# Schematic_v1_0.net
KiCad netlist of a schematic drawn in EAGLE
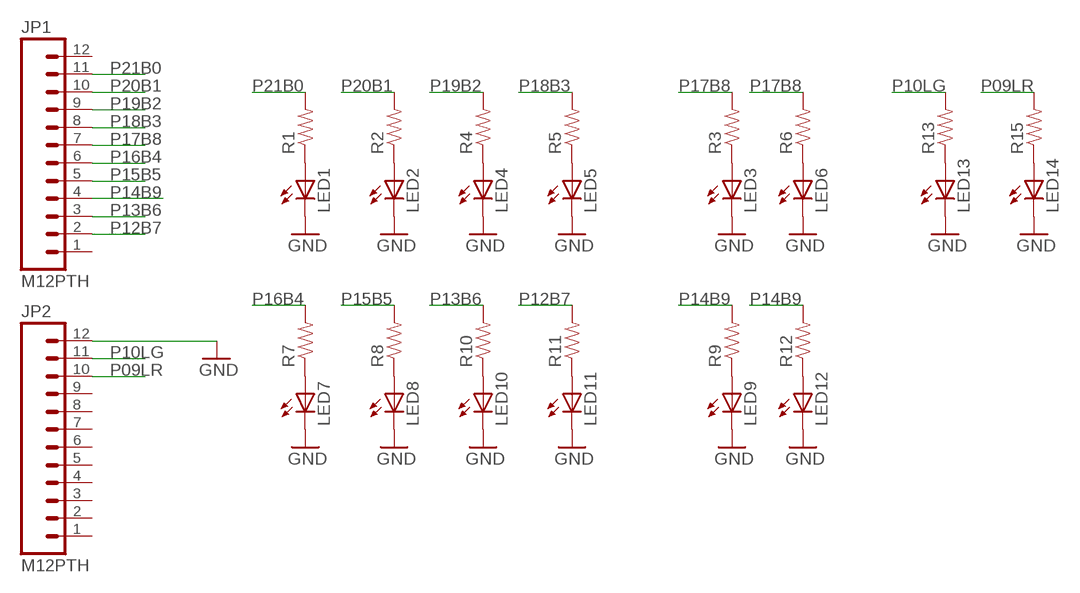
[diagram p0: schematic, sheet 1]

(export (version "E")
  (design (tool "Eeschema 10.0.6"))
  (components
    (comp (ref "JP1")
      (value "M12PTH")
      (footprint "eagle-import:1X12")
      (libsource (lib "eagle-import") (part "M12PTH"))
    )
    (comp (ref "JP2")
      (value "M12PTH")
      (footprint "eagle-import:1X12")
      (libsource (lib "eagle-import") (part "M12PTH"))
    )
    (comp (ref "LED1")
      (value "LEDCHIPLED_0805")
      (footprint "eagle-import:CHIPLED_0805")
      (libsource (lib "eagle-import") (part "LEDCHIPLED_0805"))
    )
    (comp (ref "LED2")
      (value "LEDCHIPLED_0805")
      (footprint "eagle-import:CHIPLED_0805")
      (libsource (lib "eagle-import") (part "LEDCHIPLED_0805"))
    )
    (comp (ref "LED3")
      (value "LEDCHIPLED_0805")
      (footprint "eagle-import:CHIPLED_0805")
      (libsource (lib "eagle-import") (part "LEDCHIPLED_0805"))
    )
    (comp (ref "LED4")
      (value "LEDCHIPLED_0805")
      (footprint "eagle-import:CHIPLED_0805")
      (libsource (lib "eagle-import") (part "LEDCHIPLED_0805"))
    )
    (comp (ref "LED5")
      (value "LEDCHIPLED_0805")
      (footprint "eagle-import:CHIPLED_0805")
      (libsource (lib "eagle-import") (part "LEDCHIPLED_0805"))
    )
    (comp (ref "LED6")
      (value "LEDCHIPLED_0805")
      (footprint "eagle-import:CHIPLED_0805")
      (libsource (lib "eagle-import") (part "LEDCHIPLED_0805"))
    )
    (comp (ref "LED7")
      (value "LEDCHIPLED_0805")
      (footprint "eagle-import:CHIPLED_0805")
      (libsource (lib "eagle-import") (part "LEDCHIPLED_0805"))
    )
    (comp (ref "LED8")
      (value "LEDCHIPLED_0805")
      (footprint "eagle-import:CHIPLED_0805")
      (libsource (lib "eagle-import") (part "LEDCHIPLED_0805"))
    )
    (comp (ref "LED9")
      (value "LEDCHIPLED_0805")
      (footprint "eagle-import:CHIPLED_0805")
      (libsource (lib "eagle-import") (part "LEDCHIPLED_0805"))
    )
    (comp (ref "LED10")
      (value "LEDCHIPLED_0805")
      (footprint "eagle-import:CHIPLED_0805")
      (libsource (lib "eagle-import") (part "LEDCHIPLED_0805"))
    )
    (comp (ref "LED11")
      (value "LEDCHIPLED_0805")
      (footprint "eagle-import:CHIPLED_0805")
      (libsource (lib "eagle-import") (part "LEDCHIPLED_0805"))
    )
    (comp (ref "LED12")
      (value "LEDCHIPLED_0805")
      (footprint "eagle-import:CHIPLED_0805")
      (libsource (lib "eagle-import") (part "LEDCHIPLED_0805"))
    )
    (comp (ref "LED13")
      (value "LEDCHIPLED_0805")
      (footprint "eagle-import:CHIPLED_0805")
      (libsource (lib "eagle-import") (part "LEDCHIPLED_0805"))
    )
    (comp (ref "LED14")
      (value "LEDCHIPLED_0805")
      (footprint "eagle-import:CHIPLED_0805")
      (libsource (lib "eagle-import") (part "LEDCHIPLED_0805"))
    )
    (comp (ref "R1")
      (value "RESISTOR0603-RES")
      (footprint "eagle-import:0603-RES")
      (libsource (lib "eagle-import") (part "RESISTOR0603-RES"))
    )
    (comp (ref "R2")
      (value "RESISTOR0603-RES")
      (footprint "eagle-import:0603-RES")
      (libsource (lib "eagle-import") (part "RESISTOR0603-RES"))
    )
    (comp (ref "R3")
      (value "RESISTOR0603-RES")
      (footprint "eagle-import:0603-RES")
      (libsource (lib "eagle-import") (part "RESISTOR0603-RES"))
    )
    (comp (ref "R4")
      (value "RESISTOR0603-RES")
      (footprint "eagle-import:0603-RES")
      (libsource (lib "eagle-import") (part "RESISTOR0603-RES"))
    )
    (comp (ref "R5")
      (value "RESISTOR0603-RES")
      (footprint "eagle-import:0603-RES")
      (libsource (lib "eagle-import") (part "RESISTOR0603-RES"))
    )
    (comp (ref "R6")
      (value "RESISTOR0603-RES")
      (footprint "eagle-import:0603-RES")
      (libsource (lib "eagle-import") (part "RESISTOR0603-RES"))
    )
    (comp (ref "R7")
      (value "RESISTOR0603-RES")
      (footprint "eagle-import:0603-RES")
      (libsource (lib "eagle-import") (part "RESISTOR0603-RES"))
    )
    (comp (ref "R8")
      (value "RESISTOR0603-RES")
      (footprint "eagle-import:0603-RES")
      (libsource (lib "eagle-import") (part "RESISTOR0603-RES"))
    )
    (comp (ref "R9")
      (value "RESISTOR0603-RES")
      (footprint "eagle-import:0603-RES")
      (libsource (lib "eagle-import") (part "RESISTOR0603-RES"))
    )
    (comp (ref "R10")
      (value "RESISTOR0603-RES")
      (footprint "eagle-import:0603-RES")
      (libsource (lib "eagle-import") (part "RESISTOR0603-RES"))
    )
    (comp (ref "R11")
      (value "RESISTOR0603-RES")
      (footprint "eagle-import:0603-RES")
      (libsource (lib "eagle-import") (part "RESISTOR0603-RES"))
    )
    (comp (ref "R12")
      (value "RESISTOR0603-RES")
      (footprint "eagle-import:0603-RES")
      (libsource (lib "eagle-import") (part "RESISTOR0603-RES"))
    )
    (comp (ref "R13")
      (value "RESISTOR0603-RES")
      (footprint "eagle-import:0603-RES")
      (libsource (lib "eagle-import") (part "RESISTOR0603-RES"))
    )
    (comp (ref "R15")
      (value "RESISTOR0603-RES")
      (footprint "eagle-import:0603-RES")
      (libsource (lib "eagle-import") (part "RESISTOR0603-RES"))
    )
  )
  (nets
    (net (code "1") (name "/P09LR") (class "Default")
      (node (ref "JP2") (pin "10") (pinfunction "10_10") (pintype "passive"))
      (node (ref "R15") (pin "2") (pinfunction "2_2") (pintype "passive"))
    )
    (net (code "2") (name "/P10LG") (class "Default")
      (node (ref "JP2") (pin "11") (pinfunction "11_11") (pintype "passive"))
      (node (ref "R13") (pin "2") (pinfunction "2_2") (pintype "passive"))
    )
    (net (code "3") (name "/P12B7") (class "Default")
      (node (ref "JP1") (pin "2") (pinfunction "2_2") (pintype "passive"))
      (node (ref "R11") (pin "2") (pinfunction "2_2") (pintype "passive"))
    )
    (net (code "4") (name "/P13B6") (class "Default")
      (node (ref "JP1") (pin "3") (pinfunction "3_3") (pintype "passive"))
      (node (ref "R10") (pin "2") (pinfunction "2_2") (pintype "passive"))
    )
    (net (code "5") (name "/P14B9") (class "Default")
      (node (ref "JP1") (pin "4") (pinfunction "4_4") (pintype "passive"))
      (node (ref "R12") (pin "2") (pinfunction "2_2") (pintype "passive"))
      (node (ref "R9") (pin "2") (pinfunction "2_2") (pintype "passive"))
    )
    (net (code "6") (name "/P15B5") (class "Default")
      (node (ref "JP1") (pin "5") (pinfunction "5_5") (pintype "passive"))
      (node (ref "R8") (pin "2") (pinfunction "2_2") (pintype "passive"))
    )
    (net (code "7") (name "/P16B4") (class "Default")
      (node (ref "JP1") (pin "6") (pinfunction "6_6") (pintype "passive"))
      (node (ref "R7") (pin "2") (pinfunction "2_2") (pintype "passive"))
    )
    (net (code "8") (name "/P17B8") (class "Default")
      (node (ref "JP1") (pin "7") (pinfunction "7_7") (pintype "passive"))
      (node (ref "R3") (pin "2") (pinfunction "2_2") (pintype "passive"))
      (node (ref "R6") (pin "2") (pinfunction "2_2") (pintype "passive"))
    )
    (net (code "9") (name "/P18B3") (class "Default")
      (node (ref "JP1") (pin "8") (pinfunction "8_8") (pintype "passive"))
      (node (ref "R5") (pin "2") (pinfunction "2_2") (pintype "passive"))
    )
    (net (code "10") (name "/P19B2") (class "Default")
      (node (ref "JP1") (pin "9") (pinfunction "9_9") (pintype "passive"))
      (node (ref "R4") (pin "2") (pinfunction "2_2") (pintype "passive"))
    )
    (net (code "11") (name "/P20B1") (class "Default")
      (node (ref "JP1") (pin "10") (pinfunction "10_10") (pintype "passive"))
      (node (ref "R2") (pin "2") (pinfunction "2_2") (pintype "passive"))
    )
    (net (code "12") (name "/P21B0") (class "Default")
      (node (ref "JP1") (pin "11") (pinfunction "11_11") (pintype "passive"))
      (node (ref "R1") (pin "2") (pinfunction "2_2") (pintype "passive"))
    )
    (net (code "13") (name "GND") (class "Default")
      (node (ref "JP2") (pin "12") (pinfunction "12_12") (pintype "passive"))
      (node (ref "LED1") (pin "C") (pinfunction "C_C") (pintype "passive"))
      (node (ref "LED10") (pin "C") (pinfunction "C_C") (pintype "passive"))
      (node (ref "LED11") (pin "C") (pinfunction "C_C") (pintype "passive"))
      (node (ref "LED12") (pin "C") (pinfunction "C_C") (pintype "passive"))
      (node (ref "LED13") (pin "C") (pinfunction "C_C") (pintype "passive"))
      (node (ref "LED14") (pin "C") (pinfunction "C_C") (pintype "passive"))
      (node (ref "LED2") (pin "C") (pinfunction "C_C") (pintype "passive"))
      (node (ref "LED3") (pin "C") (pinfunction "C_C") (pintype "passive"))
      (node (ref "LED4") (pin "C") (pinfunction "C_C") (pintype "passive"))
      (node (ref "LED5") (pin "C") (pinfunction "C_C") (pintype "passive"))
      (node (ref "LED6") (pin "C") (pinfunction "C_C") (pintype "passive"))
      (node (ref "LED7") (pin "C") (pinfunction "C_C") (pintype "passive"))
      (node (ref "LED8") (pin "C") (pinfunction "C_C") (pintype "passive"))
      (node (ref "LED9") (pin "C") (pinfunction "C_C") (pintype "passive"))
    )
    (net (code "14") (name "Net-(LED1-PadA)") (class "Default")
      (node (ref "LED1") (pin "A") (pinfunction "A_A") (pintype "passive"))
      (node (ref "R1") (pin "1") (pinfunction "1_1") (pintype "passive"))
    )
    (net (code "15") (name "Net-(LED2-PadA)") (class "Default")
      (node (ref "LED2") (pin "A") (pinfunction "A_A") (pintype "passive"))
      (node (ref "R2") (pin "1") (pinfunction "1_1") (pintype "passive"))
    )
    (net (code "16") (name "Net-(LED3-PadA)") (class "Default")
      (node (ref "LED3") (pin "A") (pinfunction "A_A") (pintype "passive"))
      (node (ref "R3") (pin "1") (pinfunction "1_1") (pintype "passive"))
    )
    (net (code "17") (name "Net-(LED4-PadA)") (class "Default")
      (node (ref "LED4") (pin "A") (pinfunction "A_A") (pintype "passive"))
      (node (ref "R4") (pin "1") (pinfunction "1_1") (pintype "passive"))
    )
    (net (code "18") (name "Net-(LED5-PadA)") (class "Default")
      (node (ref "LED5") (pin "A") (pinfunction "A_A") (pintype "passive"))
      (node (ref "R5") (pin "1") (pinfunction "1_1") (pintype "passive"))
    )
    (net (code "19") (name "Net-(LED6-PadA)") (class "Default")
      (node (ref "LED6") (pin "A") (pinfunction "A_A") (pintype "passive"))
      (node (ref "R6") (pin "1") (pinfunction "1_1") (pintype "passive"))
    )
    (net (code "20") (name "Net-(LED7-PadA)") (class "Default")
      (node (ref "LED7") (pin "A") (pinfunction "A_A") (pintype "passive"))
      (node (ref "R7") (pin "1") (pinfunction "1_1") (pintype "passive"))
    )
    (net (code "21") (name "Net-(LED8-PadA)") (class "Default")
      (node (ref "LED8") (pin "A") (pinfunction "A_A") (pintype "passive"))
      (node (ref "R8") (pin "1") (pinfunction "1_1") (pintype "passive"))
    )
    (net (code "22") (name "Net-(LED9-PadA)") (class "Default")
      (node (ref "LED9") (pin "A") (pinfunction "A_A") (pintype "passive"))
      (node (ref "R9") (pin "1") (pinfunction "1_1") (pintype "passive"))
    )
    (net (code "23") (name "Net-(LED10-PadA)") (class "Default")
      (node (ref "LED10") (pin "A") (pinfunction "A_A") (pintype "passive"))
      (node (ref "R10") (pin "1") (pinfunction "1_1") (pintype "passive"))
    )
    (net (code "24") (name "Net-(LED11-PadA)") (class "Default")
      (node (ref "LED11") (pin "A") (pinfunction "A_A") (pintype "passive"))
      (node (ref "R11") (pin "1") (pinfunction "1_1") (pintype "passive"))
    )
    (net (code "25") (name "Net-(LED12-PadA)") (class "Default")
      (node (ref "LED12") (pin "A") (pinfunction "A_A") (pintype "passive"))
      (node (ref "R12") (pin "1") (pinfunction "1_1") (pintype "passive"))
    )
    (net (code "26") (name "Net-(LED13-PadA)") (class "Default")
      (node (ref "LED13") (pin "A") (pinfunction "A_A") (pintype "passive"))
      (node (ref "R13") (pin "1") (pinfunction "1_1") (pintype "passive"))
    )
    (net (code "27") (name "Net-(LED14-PadA)") (class "Default")
      (node (ref "LED14") (pin "A") (pinfunction "A_A") (pintype "passive"))
      (node (ref "R15") (pin "1") (pinfunction "1_1") (pintype "passive"))
    )
    (net (code "28") (name "unconnected-(JP1-Pad1)") (class "Default")
      (node (ref "JP1") (pin "1") (pinfunction "1_1") (pintype "passive"))
    )
    (net (code "29") (name "unconnected-(JP1-Pad12)") (class "Default")
      (node (ref "JP1") (pin "12") (pinfunction "12_12") (pintype "passive"))
    )
    (net (code "30") (name "unconnected-(JP2-Pad1)") (class "Default")
      (node (ref "JP2") (pin "1") (pinfunction "1_1") (pintype "passive"))
    )
    (net (code "31") (name "unconnected-(JP2-Pad2)") (class "Default")
      (node (ref "JP2") (pin "2") (pinfunction "2_2") (pintype "passive"))
    )
    (net (code "32") (name "unconnected-(JP2-Pad3)") (class "Default")
      (node (ref "JP2") (pin "3") (pinfunction "3_3") (pintype "passive"))
    )
    (net (code "33") (name "unconnected-(JP2-Pad4)") (class "Default")
      (node (ref "JP2") (pin "4") (pinfunction "4_4") (pintype "passive"))
    )
    (net (code "34") (name "unconnected-(JP2-Pad5)") (class "Default")
      (node (ref "JP2") (pin "5") (pinfunction "5_5") (pintype "passive"))
    )
    (net (code "35") (name "unconnected-(JP2-Pad6)") (class "Default")
      (node (ref "JP2") (pin "6") (pinfunction "6_6") (pintype "passive"))
    )
    (net (code "36") (name "unconnected-(JP2-Pad7)") (class "Default")
      (node (ref "JP2") (pin "7") (pinfunction "7_7") (pintype "passive"))
    )
    (net (code "37") (name "unconnected-(JP2-Pad8)") (class "Default")
      (node (ref "JP2") (pin "8") (pinfunction "8_8") (pintype "passive"))
    )
    (net (code "38") (name "unconnected-(JP2-Pad9)") (class "Default")
      (node (ref "JP2") (pin "9") (pinfunction "9_9") (pintype "passive"))
    )
  )
)
